# BackscatterPlantSensor_v5.net
KiCad netlist of a schematic drawn in EAGLE
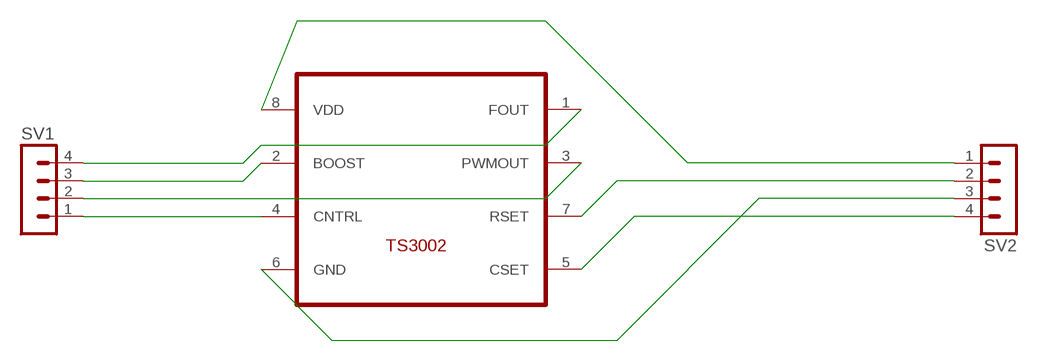
[diagram p0: schematic, sheet 1]

(export (version "E")
  (design (tool "Eeschema 10.0.6"))
  (components
    (comp (ref "SV1")
      (value "MA04-1")
      (footprint "eagle-import:MA04-1")
      (libsource (lib "eagle-import") (part "MA04-1"))
    )
    (comp (ref "SV2")
      (value "MA04-1")
      (footprint "eagle-import:MA04-1")
      (libsource (lib "eagle-import") (part "MA04-1"))
    )
    (comp (ref "U$1")
      (value "TS3002")
      (footprint "eagle-import:TDFN22-8")
      (libsource (lib "eagle-import") (part "TS3002"))
    )
  )
  (nets
    (net (code "1") (name "Net-(U$1-BOOST)") (class "Default")
      (node (ref "SV1") (pin "3") (pinfunction "3_3") (pintype "passive"))
      (node (ref "U$1") (pin "2") (pinfunction "BOOST_2") (pintype "bidirectional"))
    )
    (net (code "2") (name "Net-(U$1-CNTRL)") (class "Default")
      (node (ref "SV1") (pin "1") (pinfunction "1_1") (pintype "passive"))
      (node (ref "U$1") (pin "4") (pinfunction "CNTRL_4") (pintype "bidirectional"))
    )
    (net (code "3") (name "Net-(U$1-CSET)") (class "Default")
      (node (ref "SV2") (pin "4") (pinfunction "4_4") (pintype "passive"))
      (node (ref "U$1") (pin "5") (pinfunction "CSET_5") (pintype "bidirectional"))
    )
    (net (code "4") (name "Net-(U$1-FOUT)") (class "Default")
      (node (ref "SV1") (pin "4") (pinfunction "4_4") (pintype "passive"))
      (node (ref "U$1") (pin "1") (pinfunction "FOUT_1") (pintype "bidirectional"))
    )
    (net (code "5") (name "Net-(U$1-GND)") (class "Default")
      (node (ref "SV2") (pin "3") (pinfunction "3_3") (pintype "passive"))
      (node (ref "U$1") (pin "6") (pinfunction "GND_6") (pintype "bidirectional"))
    )
    (net (code "6") (name "Net-(U$1-PWMOUT)") (class "Default")
      (node (ref "SV1") (pin "2") (pinfunction "2_2") (pintype "passive"))
      (node (ref "U$1") (pin "3") (pinfunction "PWMOUT_3") (pintype "bidirectional"))
    )
    (net (code "7") (name "Net-(U$1-RSET)") (class "Default")
      (node (ref "SV2") (pin "2") (pinfunction "2_2") (pintype "passive"))
      (node (ref "U$1") (pin "7") (pinfunction "RSET_7") (pintype "bidirectional"))
    )
    (net (code "8") (name "Net-(U$1-VDD)") (class "Default")
      (node (ref "SV2") (pin "1") (pinfunction "1_1") (pintype "passive"))
      (node (ref "U$1") (pin "8") (pinfunction "VDD_8") (pintype "bidirectional"))
    )
  )
)
